# 08_-_CPU_-_SPI_I2C_SD_MMC.net
KiCad netlist of a schematic drawn in Altium Designer
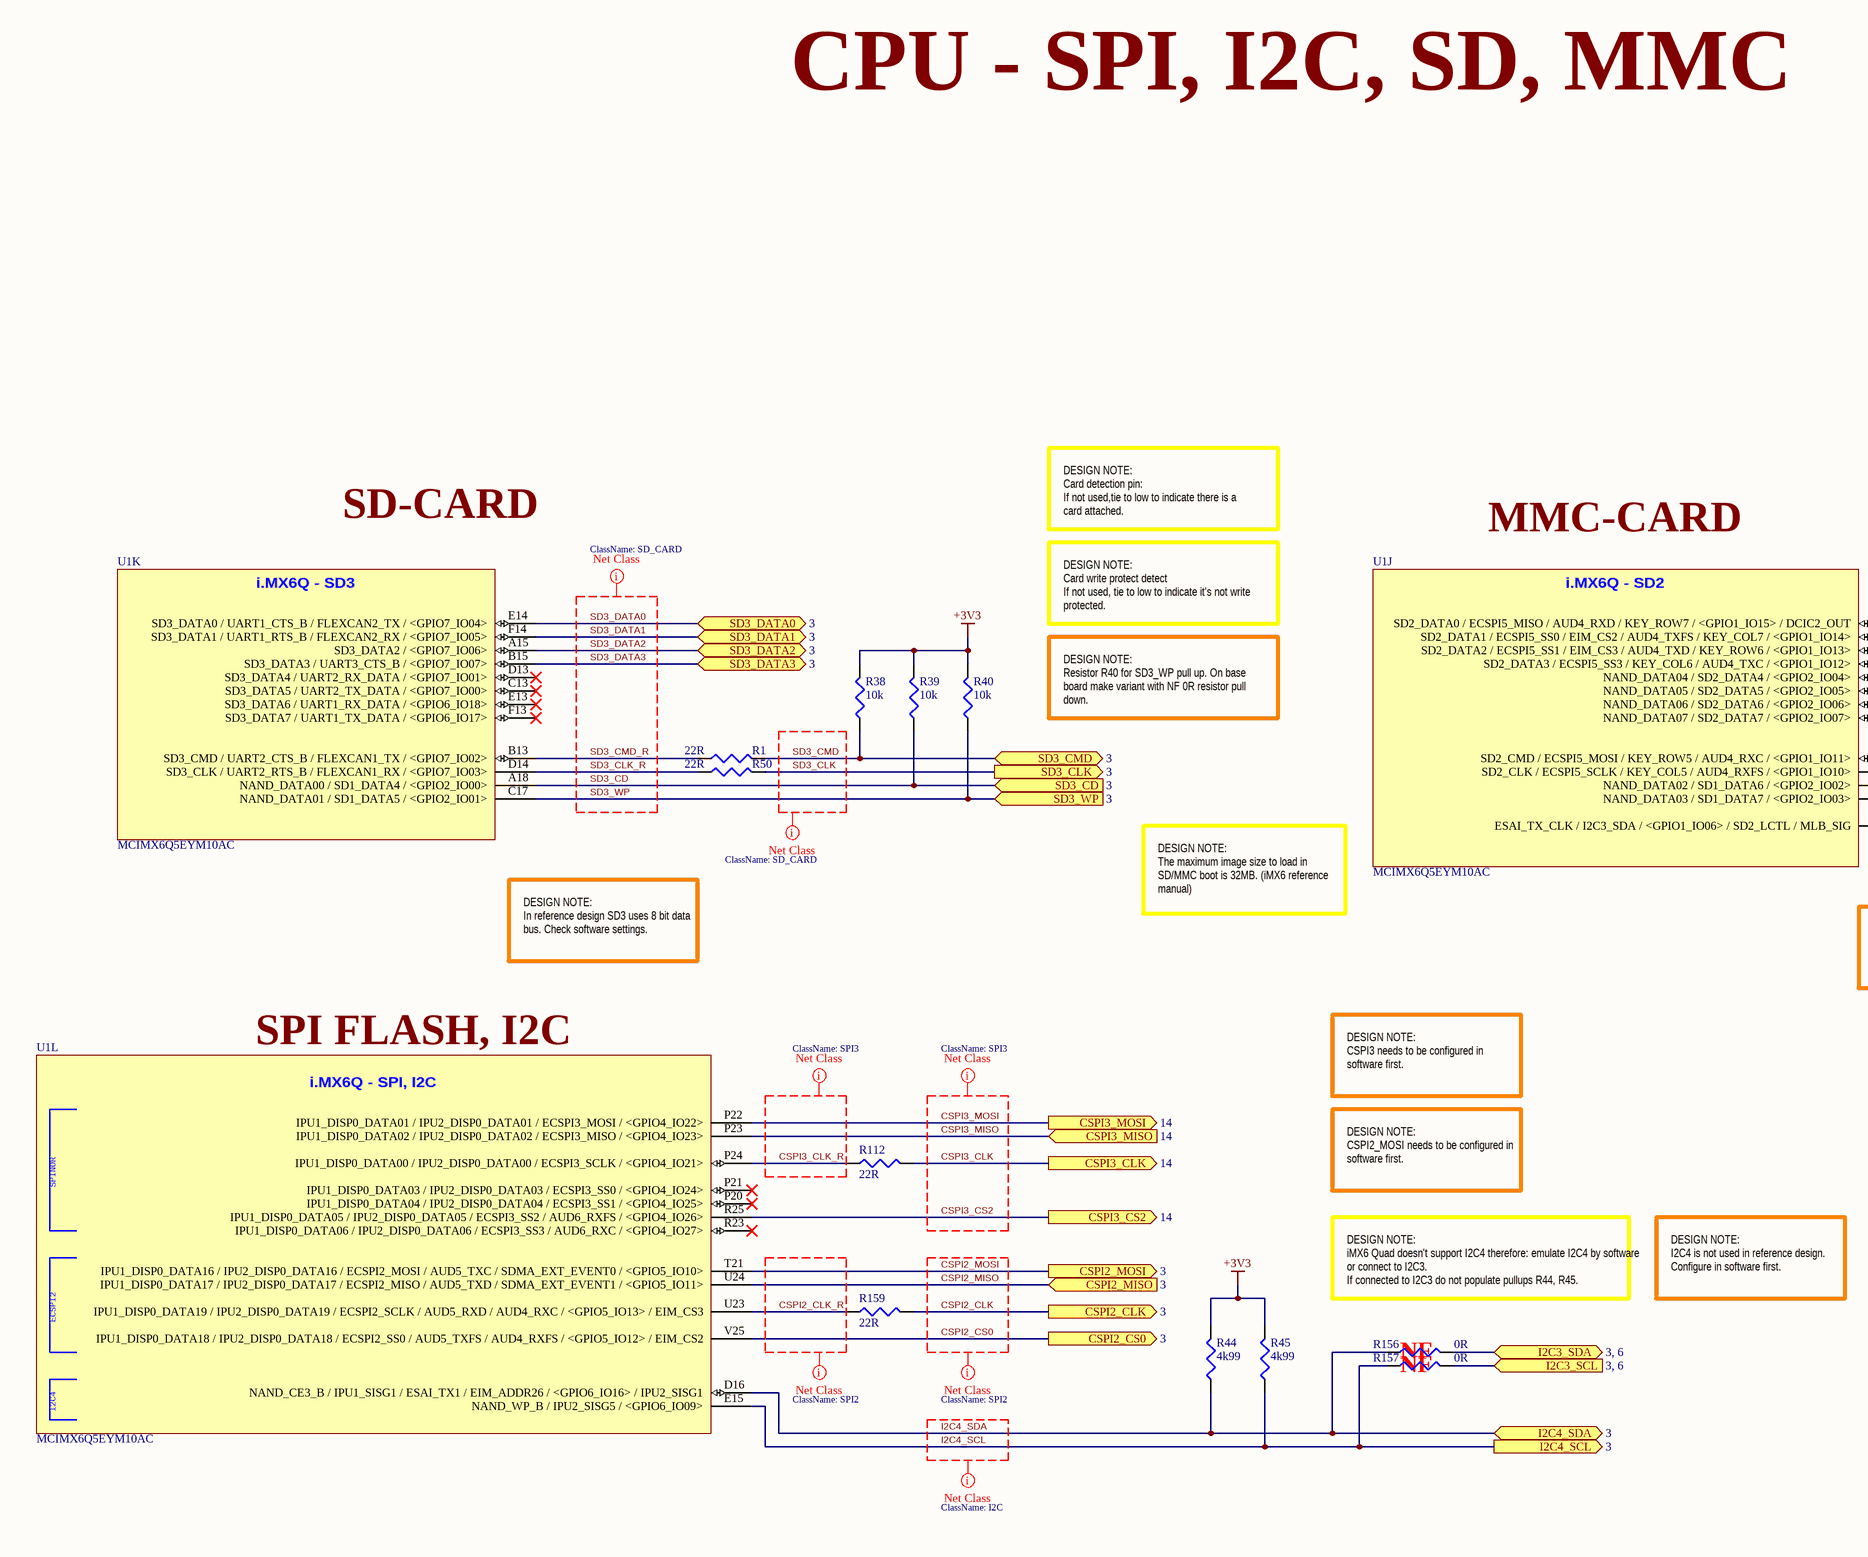
[diagram p0: [08] - CPU - SPI, I2C, SD, MMC.SchDoc, left]
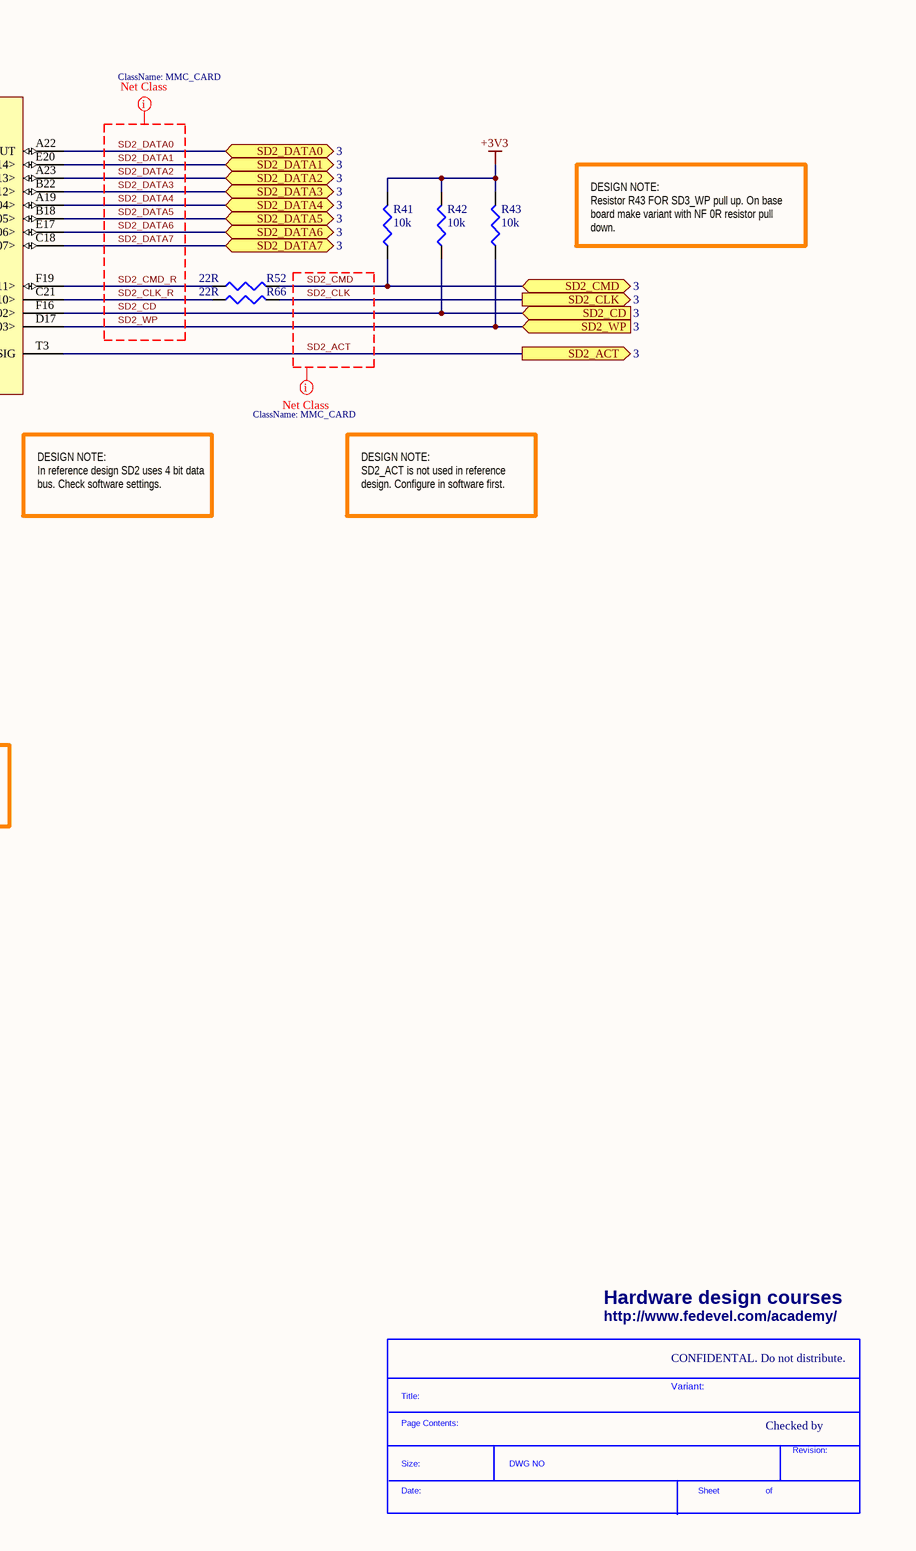
[diagram p1: [08] - CPU - SPI, I2C, SD, MMC.SchDoc, right]

(export (version "E")
  (design (tool "Eeschema 10.0.6"))
  (components
    (comp (ref "R1")
      (value "22R")
      (footprint "R0402")
      (description "RES 22.0 OHM 1/16W 1% 0402 SMD")
      (fields
        (field (name "MANUFACTURER") "Yageo")
        (field (name "MANUFACTURER PART NUMBER") "RC0402FR-0722RL")
      )
      (libsource (lib "Integrated_Library_RF_FEB_2012") (part "RC0402FR-0722RL"))
    )
    (comp (ref "R38")
      (value "10k")
      (footprint "R0402")
      (description "RES 10.0K OHM 1/16W 1% 0402 SMD")
      (fields
        (field (name "MANUFACTURER") "Yageo")
        (field (name "MANUFACTURER PART NUMBER") "RC0402FR-0710KL")
      )
      (libsource (lib "Integrated_Library_RF_FEB_2012") (part "RC0402FR-0710KL"))
    )
    (comp (ref "R39")
      (value "10k")
      (footprint "R0402")
      (description "RES 10.0K OHM 1/16W 1% 0402 SMD")
      (fields
        (field (name "MANUFACTURER") "Yageo")
        (field (name "MANUFACTURER PART NUMBER") "RC0402FR-0710KL")
      )
      (libsource (lib "Integrated_Library_RF_FEB_2012") (part "RC0402FR-0710KL"))
    )
    (comp (ref "R40")
      (value "10k")
      (footprint "R0402")
      (description "RES 10.0K OHM 1/16W 1% 0402 SMD")
      (fields
        (field (name "MANUFACTURER") "Yageo")
        (field (name "MANUFACTURER PART NUMBER") "RC0402FR-0710KL")
      )
      (libsource (lib "Integrated_Library_RF_FEB_2012") (part "RC0402FR-0710KL"))
    )
    (comp (ref "R41")
      (value "10k")
      (footprint "R0402")
      (description "RES 10.0K OHM 1/16W 1% 0402 SMD")
      (fields
        (field (name "MANUFACTURER") "Yageo")
        (field (name "MANUFACTURER PART NUMBER") "RC0402FR-0710KL")
      )
      (libsource (lib "Integrated_Library_RF_FEB_2012") (part "RC0402FR-0710KL"))
    )
    (comp (ref "R42")
      (value "10k")
      (footprint "R0402")
      (description "RES 10.0K OHM 1/16W 1% 0402 SMD")
      (fields
        (field (name "MANUFACTURER") "Yageo")
        (field (name "MANUFACTURER PART NUMBER") "RC0402FR-0710KL")
      )
      (libsource (lib "Integrated_Library_RF_FEB_2012") (part "RC0402FR-0710KL"))
    )
    (comp (ref "R43")
      (value "10k")
      (footprint "R0402")
      (description "RES 10.0K OHM 1/16W 1% 0402 SMD")
      (fields
        (field (name "MANUFACTURER") "Yageo")
        (field (name "MANUFACTURER PART NUMBER") "RC0402FR-0710KL")
      )
      (libsource (lib "Integrated_Library_RF_FEB_2012") (part "RC0402FR-0710KL"))
    )
    (comp (ref "R44")
      (value "4k99")
      (footprint "R0402")
      (description "RES TF 4.99K OHM 1% 1/16W 0402")
      (fields
        (field (name "MANUFACTURER") "Stackpole Electronics Inc")
        (field (name "MANUFACTURER PART NUMBER") "RMCF0402FT4K99")
      )
      (libsource (lib "Integrated_Library_RF_FEB_2012") (part "RMCF0402FT4K99"))
    )
    (comp (ref "R45")
      (value "4k99")
      (footprint "R0402")
      (description "RES TF 4.99K OHM 1% 1/16W 0402")
      (fields
        (field (name "MANUFACTURER") "Stackpole Electronics Inc")
        (field (name "MANUFACTURER PART NUMBER") "RMCF0402FT4K99")
      )
      (libsource (lib "Integrated_Library_RF_FEB_2012") (part "RMCF0402FT4K99"))
    )
    (comp (ref "R50")
      (value "22R")
      (footprint "R0402")
      (description "RES 22.0 OHM 1/16W 1% 0402 SMD")
      (fields
        (field (name "MANUFACTURER") "Yageo")
        (field (name "MANUFACTURER PART NUMBER") "RC0402FR-0722RL")
      )
      (libsource (lib "Integrated_Library_RF_FEB_2012") (part "RC0402FR-0722RL"))
    )
    (comp (ref "R52")
      (value "22R")
      (footprint "R0402")
      (description "RES 22.0 OHM 1/16W 1% 0402 SMD")
      (fields
        (field (name "MANUFACTURER") "Yageo")
        (field (name "MANUFACTURER PART NUMBER") "RC0402FR-0722RL")
      )
      (libsource (lib "Integrated_Library_RF_FEB_2012") (part "RC0402FR-0722RL"))
    )
    (comp (ref "R66")
      (value "22R")
      (footprint "R0402")
      (description "RES 22.0 OHM 1/16W 1% 0402 SMD")
      (fields
        (field (name "MANUFACTURER") "Yageo")
        (field (name "MANUFACTURER PART NUMBER") "RC0402FR-0722RL")
      )
      (libsource (lib "Integrated_Library_RF_FEB_2012") (part "RC0402FR-0722RL"))
    )
    (comp (ref "R112")
      (value "22R")
      (footprint "R0402")
      (description "RES 22.0 OHM 1/16W 1% 0402 SMD")
      (fields
        (field (name "MANUFACTURER") "Yageo")
        (field (name "MANUFACTURER PART NUMBER") "RC0402FR-0722RL")
      )
      (libsource (lib "Integrated_Library_RF_FEB_2012") (part "RC0402FR-0722RL"))
    )
    (comp (ref "R156")
      (value "0R")
      (footprint "R0402")
      (description "RES 0.0 OHM 1/16W 0402 SMD")
      (fields
        (field (name "MANUFACTURER") "Yageo")
        (field (name "MANUFACTURER PART NUMBER") "RC0402JR-070RL")
      )
      (libsource (lib "Integrated_Library_RF_FEB_2012") (part "RC0402JR-070RL"))
    )
    (comp (ref "R157")
      (value "0R")
      (footprint "R0402")
      (description "RES 0.0 OHM 1/16W 0402 SMD")
      (fields
        (field (name "MANUFACTURER") "Yageo")
        (field (name "MANUFACTURER PART NUMBER") "RC0402JR-070RL")
      )
      (libsource (lib "Integrated_Library_RF_FEB_2012") (part "RC0402JR-070RL"))
    )
    (comp (ref "R159")
      (value "22R")
      (footprint "R0402")
      (description "RES 22.0 OHM 1/16W 1% 0402 SMD")
      (fields
        (field (name "MANUFACTURER") "Yageo")
        (field (name "MANUFACTURER PART NUMBER") "RC0402FR-0722RL")
      )
      (libsource (lib "Integrated_Library_RF_FEB_2012") (part "RC0402FR-0722RL"))
    )
    (comp (ref "U1")
      (value "MCIMX6Q5EYM10AC")
      (footprint "PBGA624")
      (description "IC MCU 32BIT ARM QUAD 624FCBGA")
      (fields
        (field (name "MANUFACTURER") "Freescale Semiconductor")
        (field (name ".CREATOR") "MM")
        (field (name ".CHECKED PCB") "MM, checked by RF")
        (field (name ".CHECKED SCH") "MM")
      )
      (libsource (lib "Schlib_RF") (part "MCIMX6Q5EYM10AC"))
    )
  )
  (nets
    (net (code "1") (name "+3V3") (class "Default")
      (node (ref "R38") (pin "2") (pinfunction "2_2") (pintype "passive"))
      (node (ref "R39") (pin "2") (pinfunction "2_2") (pintype "passive"))
      (node (ref "R40") (pin "2") (pinfunction "2_2") (pintype "passive"))
      (node (ref "R41") (pin "2") (pinfunction "2_2") (pintype "passive"))
      (node (ref "R42") (pin "2") (pinfunction "2_2") (pintype "passive"))
      (node (ref "R43") (pin "2") (pinfunction "2_2") (pintype "passive"))
      (node (ref "R44") (pin "2") (pinfunction "2_2") (pintype "passive"))
      (node (ref "R45") (pin "2") (pinfunction "2_2") (pintype "passive"))
    )
    (net (code "2") (name "/CSPI2_CLK") (class "Default")
      (node (ref "R159") (pin "2") (pinfunction "2_2") (pintype "passive"))
    )
    (net (code "3") (name "/CSPI2_CLK_R") (class "Default")
      (node (ref "R159") (pin "1") (pinfunction "1_1") (pintype "passive"))
      (node (ref "U1") (pin "U23") (pinfunction "IPU1_DISP0_DATA19_/_IPU2_DISP0_DATA19_/_ECSPI2_SCLK_/_AUD5_RXD_/_AUD4_RXC_/_<GPIO5_IO13>_/_EIM_CS3_U23") (pintype "passive"))
    )
    (net (code "4") (name "/CSPI2_CS0") (class "Default")
      (node (ref "U1") (pin "V25") (pinfunction "IPU1_DISP0_DATA18_/_IPU2_DISP0_DATA18_/_ECSPI2_SS0_/_AUD5_TXFS_/_AUD4_RXFS_/_<GPIO5_IO12>_/_EIM_CS2_V25") (pintype "passive"))
    )
    (net (code "5") (name "/CSPI2_MISO") (class "Default")
      (node (ref "U1") (pin "U24") (pinfunction "IPU1_DISP0_DATA17_/_IPU2_DISP0_DATA17_/_ECSPI2_MISO_/_AUD5_TXD_/_SDMA_EXT_EVENT1_/_<GPIO5_IO11>_U24") (pintype "passive"))
    )
    (net (code "6") (name "/CSPI2_MOSI") (class "Default")
      (node (ref "U1") (pin "T21") (pinfunction "IPU1_DISP0_DATA16_/_IPU2_DISP0_DATA16_/_ECSPI2_MOSI_/_AUD5_TXC_/_SDMA_EXT_EVENT0_/_<GPIO5_IO10>_T21") (pintype "passive"))
    )
    (net (code "7") (name "/CSPI3_CLK") (class "Default")
      (node (ref "R112") (pin "2") (pinfunction "2_2") (pintype "passive"))
    )
    (net (code "8") (name "/CSPI3_CLK_R") (class "Default")
      (node (ref "R112") (pin "1") (pinfunction "1_1") (pintype "passive"))
      (node (ref "U1") (pin "P24") (pinfunction "IPU1_DISP0_DATA00_/_IPU2_DISP0_DATA00_/_ECSPI3_SCLK_/_<GPIO4_IO21>_P24") (pintype "bidirectional"))
    )
    (net (code "9") (name "/CSPI3_CS2") (class "Default")
      (node (ref "U1") (pin "R25") (pinfunction "IPU1_DISP0_DATA05_/_IPU2_DISP0_DATA05_/_ECSPI3_SS2_/_AUD6_RXFS_/_<GPIO4_IO26>_R25") (pintype "passive"))
    )
    (net (code "10") (name "/CSPI3_MISO") (class "Default")
      (node (ref "U1") (pin "P23") (pinfunction "IPU1_DISP0_DATA02_/_IPU2_DISP0_DATA02_/_ECSPI3_MISO_/_<GPIO4_IO23>_P23") (pintype "passive"))
    )
    (net (code "11") (name "/CSPI3_MOSI") (class "Default")
      (node (ref "U1") (pin "P22") (pinfunction "IPU1_DISP0_DATA01_/_IPU2_DISP0_DATA01_/_ECSPI3_MOSI_/_<GPIO4_IO22>_P22") (pintype "passive"))
    )
    (net (code "12") (name "/I2C3_SCL") (class "Default")
      (node (ref "R157") (pin "2") (pinfunction "2_2") (pintype "passive"))
    )
    (net (code "13") (name "/I2C3_SDA") (class "Default")
      (node (ref "R156") (pin "2") (pinfunction "2_2") (pintype "passive"))
    )
    (net (code "14") (name "/I2C4_SCL") (class "Default")
      (node (ref "R157") (pin "1") (pinfunction "1_1") (pintype "passive"))
      (node (ref "R45") (pin "1") (pinfunction "1_1") (pintype "passive"))
      (node (ref "U1") (pin "E15") (pinfunction "NAND_WP_B_/_IPU2_SISG5_/_<GPIO6_IO09>_E15") (pintype "passive"))
    )
    (net (code "15") (name "/I2C4_SDA") (class "Default")
      (node (ref "R156") (pin "1") (pinfunction "1_1") (pintype "passive"))
      (node (ref "R44") (pin "1") (pinfunction "1_1") (pintype "passive"))
      (node (ref "U1") (pin "D16") (pinfunction "NAND_CE3_B_/_IPU1_SISG1_/_ESAI_TX1_/_EIM_ADDR26_/_<GPIO6_IO16>_/_IPU2_SISG1_D16") (pintype "bidirectional"))
    )
    (net (code "16") (name "/SD2_ACT") (class "Default")
      (node (ref "U1") (pin "T3") (pinfunction "ESAI_TX_CLK_/_I2C3_SDA_/_<GPIO1_IO06>_/_SD2_LCTL_/_MLB_SIG_T3") (pintype "passive"))
    )
    (net (code "17") (name "/SD2_CD") (class "Default")
      (node (ref "R42") (pin "1") (pinfunction "1_1") (pintype "passive"))
      (node (ref "U1") (pin "F16") (pinfunction "NAND_DATA02_/_SD1_DATA6_/_<GPIO2_IO02>_F16") (pintype "passive"))
    )
    (net (code "18") (name "/SD2_CLK") (class "Default")
      (node (ref "R66") (pin "2") (pinfunction "2_2") (pintype "passive"))
    )
    (net (code "19") (name "/SD2_CLK_R") (class "Default")
      (node (ref "R66") (pin "1") (pinfunction "1_1") (pintype "passive"))
      (node (ref "U1") (pin "C21") (pinfunction "SD2_CLK_/_ECSPI5_SCLK_/_KEY_COL5_/_AUD4_RXFS_/_<GPIO1_IO10>_C21") (pintype "passive"))
    )
    (net (code "20") (name "/SD2_CMD") (class "Default")
      (node (ref "R41") (pin "1") (pinfunction "1_1") (pintype "passive"))
      (node (ref "R52") (pin "2") (pinfunction "2_2") (pintype "passive"))
    )
    (net (code "21") (name "/SD2_CMD_R") (class "Default")
      (node (ref "R52") (pin "1") (pinfunction "1_1") (pintype "passive"))
      (node (ref "U1") (pin "F19") (pinfunction "SD2_CMD_/_ECSPI5_MOSI_/_KEY_ROW5_/_AUD4_RXC_/_<GPIO1_IO11>_F19") (pintype "bidirectional"))
    )
    (net (code "22") (name "/SD2_DATA0") (class "Default")
      (node (ref "U1") (pin "A22") (pinfunction "SD2_DATA0_/_ECSPI5_MISO_/_AUD4_RXD_/_KEY_ROW7_/_<GPIO1_IO15>_/_DCIC2_OUT_A22") (pintype "bidirectional"))
    )
    (net (code "23") (name "/SD2_DATA1") (class "Default")
      (node (ref "U1") (pin "E20") (pinfunction "SD2_DATA1_/_ECSPI5_SS0_/_EIM_CS2_/_AUD4_TXFS_/_KEY_COL7_/_<GPIO1_IO14>_E20") (pintype "bidirectional"))
    )
    (net (code "24") (name "/SD2_DATA2") (class "Default")
      (node (ref "U1") (pin "A23") (pinfunction "SD2_DATA2_/_ECSPI5_SS1_/_EIM_CS3_/_AUD4_TXD_/_KEY_ROW6_/_<GPIO1_IO13>_A23") (pintype "bidirectional"))
    )
    (net (code "25") (name "/SD2_DATA3") (class "Default")
      (node (ref "U1") (pin "B22") (pinfunction "SD2_DATA3_/_ECSPI5_SS3_/_KEY_COL6_/_AUD4_TXC_/_<GPIO1_IO12>_B22") (pintype "bidirectional"))
    )
    (net (code "26") (name "/SD2_DATA4") (class "Default")
      (node (ref "U1") (pin "A19") (pinfunction "NAND_DATA04_/_SD2_DATA4_/_<GPIO2_IO04>_A19") (pintype "bidirectional"))
    )
    (net (code "27") (name "/SD2_DATA5") (class "Default")
      (node (ref "U1") (pin "B18") (pinfunction "NAND_DATA05_/_SD2_DATA5_/_<GPIO2_IO05>_B18") (pintype "bidirectional"))
    )
    (net (code "28") (name "/SD2_DATA6") (class "Default")
      (node (ref "U1") (pin "E17") (pinfunction "NAND_DATA06_/_SD2_DATA6_/_<GPIO2_IO06>_E17") (pintype "bidirectional"))
    )
    (net (code "29") (name "/SD2_DATA7") (class "Default")
      (node (ref "U1") (pin "C18") (pinfunction "NAND_DATA07_/_SD2_DATA7_/_<GPIO2_IO07>_C18") (pintype "bidirectional"))
    )
    (net (code "30") (name "/SD2_WP") (class "Default")
      (node (ref "R43") (pin "1") (pinfunction "1_1") (pintype "passive"))
      (node (ref "U1") (pin "D17") (pinfunction "NAND_DATA03_/_SD1_DATA7_/_<GPIO2_IO03>_D17") (pintype "passive"))
    )
    (net (code "31") (name "/SD3_CD") (class "Default")
      (node (ref "R39") (pin "1") (pinfunction "1_1") (pintype "passive"))
      (node (ref "U1") (pin "A18") (pinfunction "NAND_DATA00_/_SD1_DATA4_/_<GPIO2_IO00>_A18") (pintype "passive"))
    )
    (net (code "32") (name "/SD3_CLK") (class "Default")
      (node (ref "R50") (pin "2") (pinfunction "2_2") (pintype "passive"))
    )
    (net (code "33") (name "/SD3_CLK_R") (class "Default")
      (node (ref "R50") (pin "1") (pinfunction "1_1") (pintype "passive"))
      (node (ref "U1") (pin "D14") (pinfunction "SD3_CLK_/_UART2_RTS_B_/_FLEXCAN1_RX_/_<GPIO7_IO03>_D14") (pintype "passive"))
    )
    (net (code "34") (name "/SD3_CMD") (class "Default")
      (node (ref "R1") (pin "2") (pinfunction "2_2") (pintype "passive"))
      (node (ref "R38") (pin "1") (pinfunction "1_1") (pintype "passive"))
    )
    (net (code "35") (name "/SD3_CMD_R") (class "Default")
      (node (ref "R1") (pin "1") (pinfunction "1_1") (pintype "passive"))
      (node (ref "U1") (pin "B13") (pinfunction "SD3_CMD_/_UART2_CTS_B_/_FLEXCAN1_TX_/_<GPIO7_IO02>_B13") (pintype "bidirectional"))
    )
    (net (code "36") (name "/SD3_DATA0") (class "Default")
      (node (ref "U1") (pin "E14") (pinfunction "SD3_DATA0_/_UART1_CTS_B_/_FLEXCAN2_TX_/_<GPIO7_IO04>_E14") (pintype "bidirectional"))
    )
    (net (code "37") (name "/SD3_DATA1") (class "Default")
      (node (ref "U1") (pin "F14") (pinfunction "SD3_DATA1_/_UART1_RTS_B_/_FLEXCAN2_RX_/_<GPIO7_IO05>_F14") (pintype "bidirectional"))
    )
    (net (code "38") (name "/SD3_DATA2") (class "Default")
      (node (ref "U1") (pin "A15") (pinfunction "SD3_DATA2_/_<GPIO7_IO06>_A15") (pintype "bidirectional"))
    )
    (net (code "39") (name "/SD3_DATA3") (class "Default")
      (node (ref "U1") (pin "B15") (pinfunction "SD3_DATA3_/_UART3_CTS_B_/_<GPIO7_IO07>_B15") (pintype "bidirectional"))
    )
    (net (code "40") (name "/SD3_WP") (class "Default")
      (node (ref "R40") (pin "1") (pinfunction "1_1") (pintype "passive"))
      (node (ref "U1") (pin "C17") (pinfunction "NAND_DATA01_/_SD1_DATA5_/_<GPIO2_IO01>_C17") (pintype "passive"))
    )
    (net (code "41") (name "unconnected-(U1K-SD3_DATA4_{slash}_UART2_RX_DATA_{slash}_<GPIO7_IO01>-PadD13)") (class "Default")
      (node (ref "U1") (pin "D13") (pinfunction "SD3_DATA4_/_UART2_RX_DATA_/_<GPIO7_IO01>_D13") (pintype "bidirectional+no_connect"))
    )
    (net (code "42") (name "unconnected-(U1K-SD3_DATA5_{slash}_UART2_TX_DATA_{slash}_<GPIO7_IO00>-PadC13)") (class "Default")
      (node (ref "U1") (pin "C13") (pinfunction "SD3_DATA5_/_UART2_TX_DATA_/_<GPIO7_IO00>_C13") (pintype "bidirectional+no_connect"))
    )
    (net (code "43") (name "unconnected-(U1K-SD3_DATA6_{slash}_UART1_RX_DATA_{slash}_<GPIO6_IO18>-PadE13)") (class "Default")
      (node (ref "U1") (pin "E13") (pinfunction "SD3_DATA6_/_UART1_RX_DATA_/_<GPIO6_IO18>_E13") (pintype "bidirectional+no_connect"))
    )
    (net (code "44") (name "unconnected-(U1K-SD3_DATA7_{slash}_UART1_TX_DATA_{slash}_<GPIO6_IO17>-PadF13)") (class "Default")
      (node (ref "U1") (pin "F13") (pinfunction "SD3_DATA7_/_UART1_TX_DATA_/_<GPIO6_IO17>_F13") (pintype "bidirectional+no_connect"))
    )
    (net (code "45") (name "unconnected-(U1L-IPU1_DISP0_DATA03_{slash}_IPU2_DISP0_DATA03_{slash}_ECSPI3_SS0_{slash}_<GPIO4_IO24>-PadP21)") (class "Default")
      (node (ref "U1") (pin "P21") (pinfunction "IPU1_DISP0_DATA03_/_IPU2_DISP0_DATA03_/_ECSPI3_SS0_/_<GPIO4_IO24>_P21") (pintype "bidirectional+no_connect"))
    )
    (net (code "46") (name "unconnected-(U1L-IPU1_DISP0_DATA04_{slash}_IPU2_DISP0_DATA04_{slash}_ECSPI3_SS1_{slash}_<GPIO4_IO25>-PadP20)") (class "Default")
      (node (ref "U1") (pin "P20") (pinfunction "IPU1_DISP0_DATA04_/_IPU2_DISP0_DATA04_/_ECSPI3_SS1_/_<GPIO4_IO25>_P20") (pintype "bidirectional+no_connect"))
    )
    (net (code "47") (name "unconnected-(U1L-IPU1_DISP0_DATA06_{slash}_IPU2_DISP0_DATA06_{slash}_ECSPI3_SS3_{slash}_AUD6_RXC_{slash}_<GPIO4_IO27>-PadR23)") (class "Default")
      (node (ref "U1") (pin "R23") (pinfunction "IPU1_DISP0_DATA06_/_IPU2_DISP0_DATA06_/_ECSPI3_SS3_/_AUD6_RXC_/_<GPIO4_IO27>_R23") (pintype "bidirectional+no_connect"))
    )
  )
)
